# design.net
KiCad netlist of a schematic drawn in Altium Designer
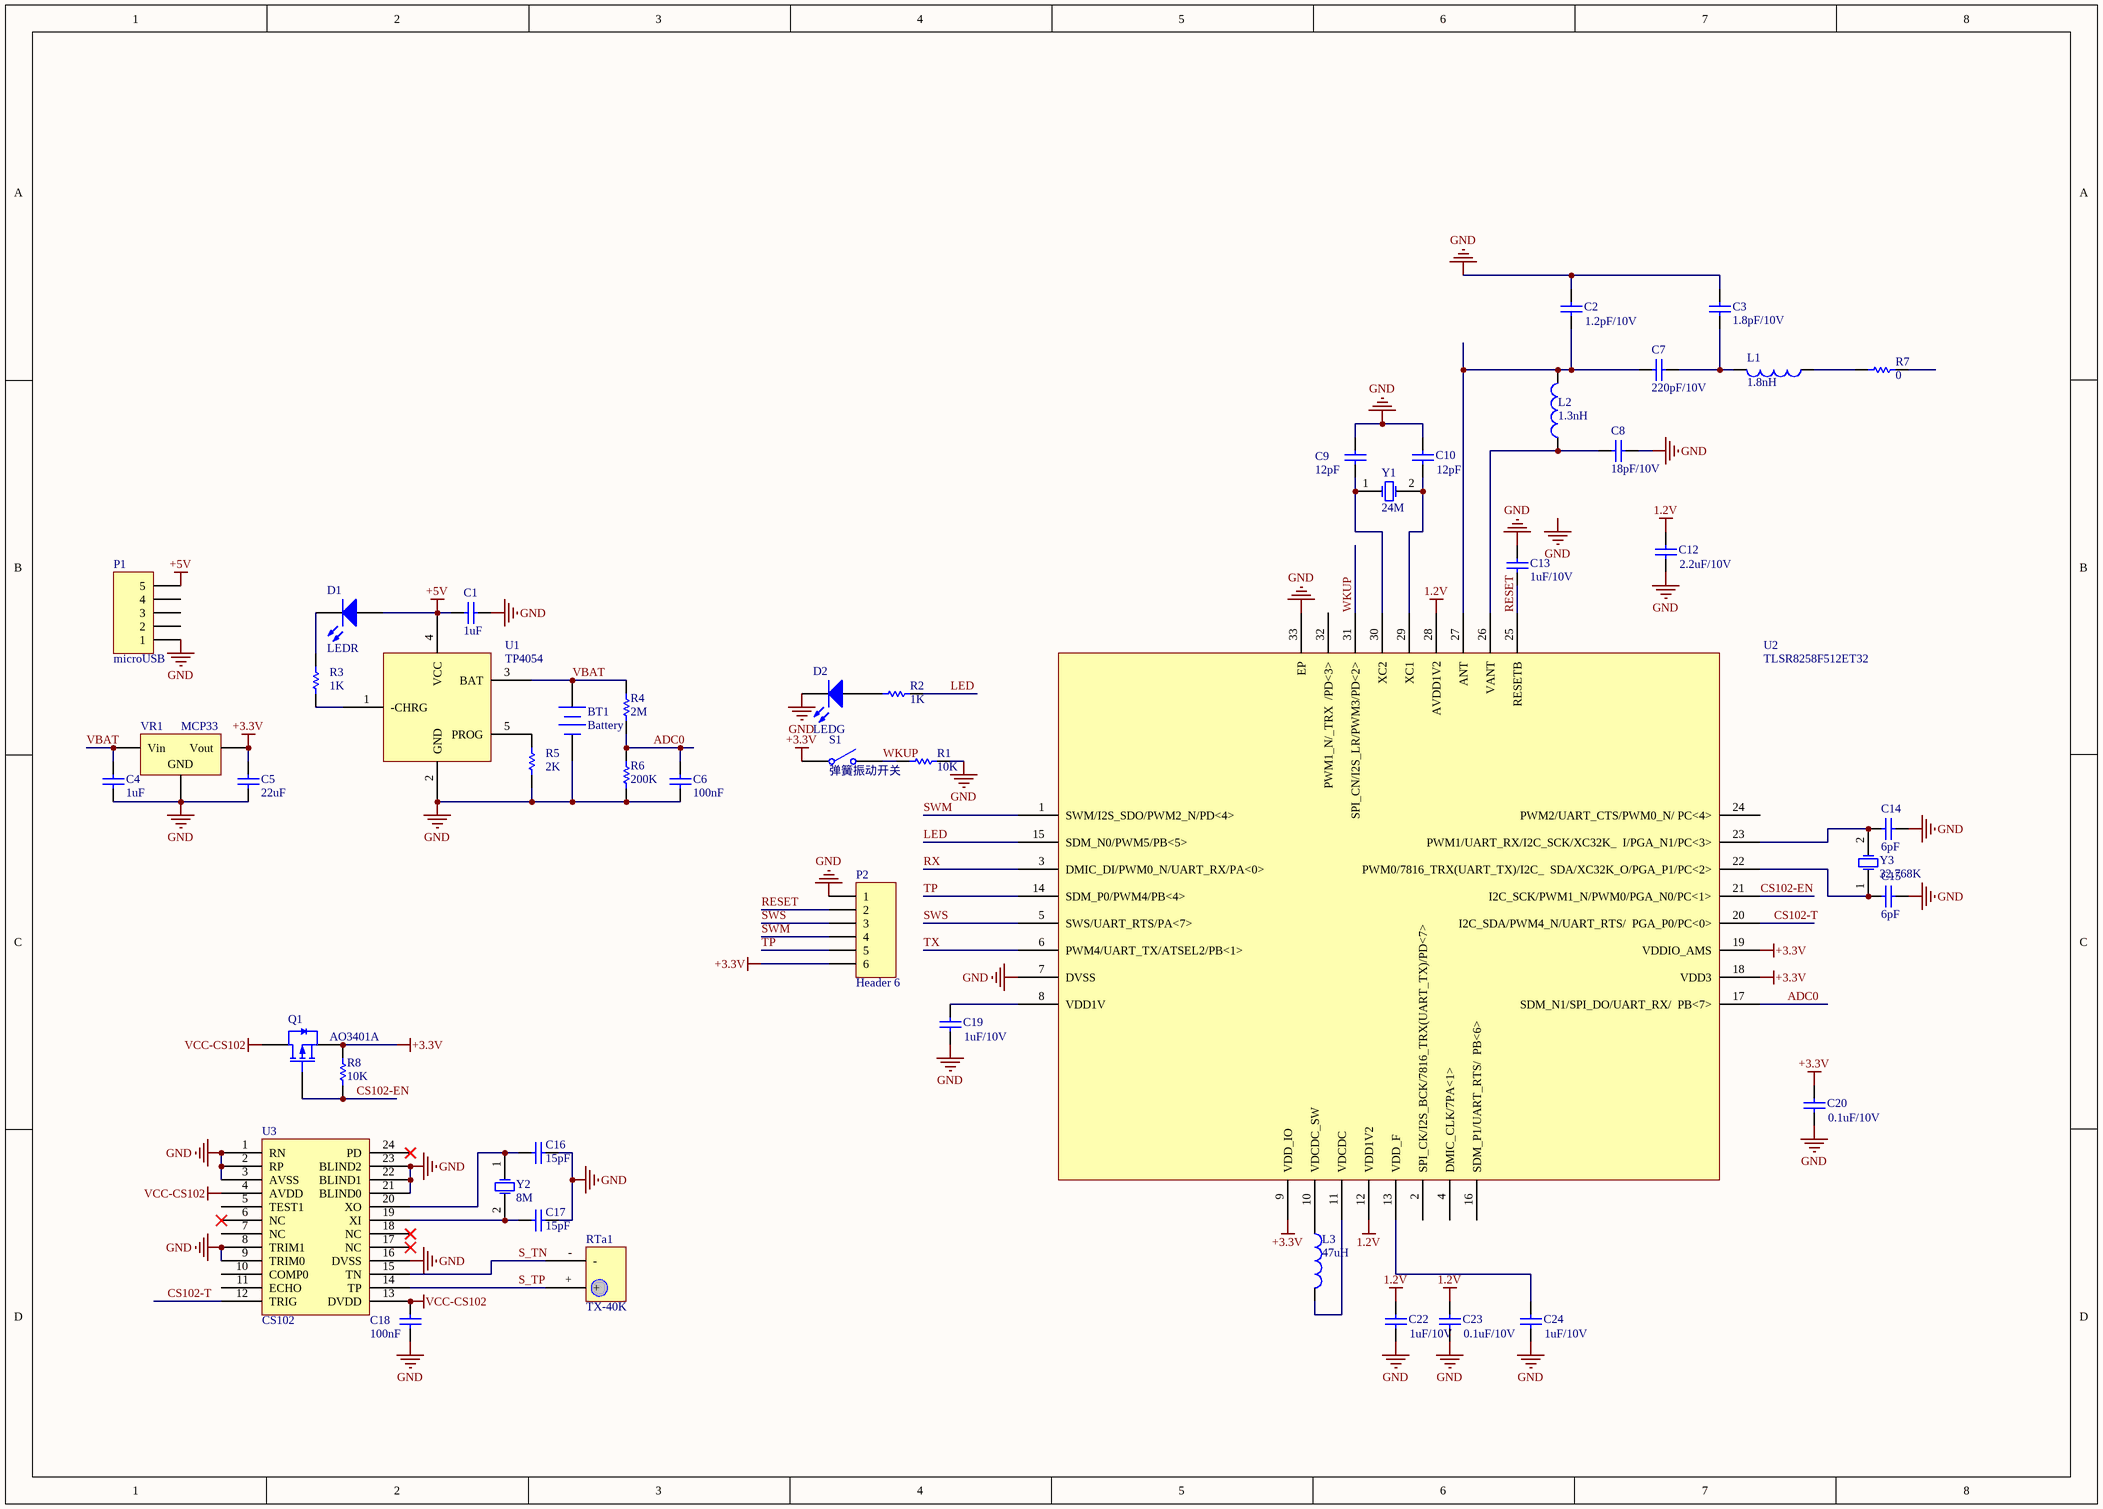
[diagram p0: 发送端原理图.SchDoc]

(export (version "E")
  (design (tool "Eeschema 10.0.6"))
  (components
    (comp (ref "BT1")
      (value "Battery")
      (footprint "BT")
      (description "Multicell Battery")
      (fields (field (name "PUBLISHER") "Altium Limited"))
      (libsource (lib "Miscellaneous Devices") (part "Battery"))
    )
    (comp (ref "C1")
      (value "1uF")
      (description "Capacitor")
      (fields (field (name "PUBLISHER") "Altium Limited"))
      (libsource (lib "Miscellaneous Devices") (part "Cap"))
    )
    (comp (ref "C2")
      (value "1.2pF/10V")
      (footprint "0402")
      (description "Capacitor")
      (fields (field (name "PUBLISHER") "Altium Limited"))
      (libsource (lib "Miscellaneous Devices") (part "Cap"))
    )
    (comp (ref "C3")
      (value "1.8pF/10V")
      (footprint "0402")
      (description "Capacitor")
      (fields (field (name "PUBLISHER") "Altium Limited"))
      (libsource (lib "Miscellaneous Devices") (part "Cap"))
    )
    (comp (ref "C4")
      (value "1uF")
      (description "Capacitor")
      (fields (field (name "PUBLISHER") "Altium Limited"))
      (libsource (lib "Miscellaneous Devices") (part "Cap"))
    )
    (comp (ref "C5")
      (value "22uF")
      (description "Capacitor")
      (fields (field (name "PUBLISHER") "Altium Limited"))
      (libsource (lib "Miscellaneous Devices") (part "Cap"))
    )
    (comp (ref "C6")
      (value "100nF")
      (description "Capacitor")
      (fields (field (name "PUBLISHER") "Altium Limited"))
      (libsource (lib "Miscellaneous Devices") (part "Cap"))
    )
    (comp (ref "C7")
      (value "220pF/10V")
      (footprint "0402")
      (description "Capacitor")
      (fields (field (name "PUBLISHER") "Altium Limited"))
      (libsource (lib "Miscellaneous Devices") (part "Cap"))
    )
    (comp (ref "C8")
      (value "18pF/10V")
      (footprint "0402")
      (description "Capacitor")
      (fields (field (name "PUBLISHER") "Altium Limited"))
      (libsource (lib "Miscellaneous Devices") (part "Cap"))
    )
    (comp (ref "C9")
      (value "12pF")
      (footprint "0402")
      (description "Capacitor")
      (fields (field (name "PUBLISHER") "Altium Limited"))
      (libsource (lib "Miscellaneous Devices") (part "Cap"))
    )
    (comp (ref "C10")
      (value "12pF")
      (footprint "0402")
      (description "Capacitor")
      (fields (field (name "PUBLISHER") "Altium Limited"))
      (libsource (lib "Miscellaneous Devices") (part "Cap"))
    )
    (comp (ref "C12")
      (value "2.2uF/10V")
      (footprint "0402")
      (description "Capacitor")
      (fields (field (name "PUBLISHER") "Altium Limited"))
      (libsource (lib "Miscellaneous Devices") (part "Cap"))
    )
    (comp (ref "C13")
      (value "1uF/10V")
      (footprint "0402")
      (description "Capacitor")
      (fields (field (name "PUBLISHER") "Altium Limited"))
      (libsource (lib "Miscellaneous Devices") (part "Cap"))
    )
    (comp (ref "C14")
      (value "6pF")
      (footprint "0402")
      (description "Capacitor")
      (fields (field (name "PUBLISHER") "Altium Limited"))
      (libsource (lib "Miscellaneous Devices") (part "Cap"))
    )
    (comp (ref "C15")
      (value "6pF")
      (footprint "0402")
      (description "Capacitor")
      (fields (field (name "PUBLISHER") "Altium Limited"))
      (libsource (lib "Miscellaneous Devices") (part "Cap"))
    )
    (comp (ref "C16")
      (value "15pF")
      (footprint "0402")
      (description "Capacitor")
      (fields (field (name "PUBLISHER") "Altium Limited"))
      (libsource (lib "Miscellaneous Devices") (part "Cap"))
    )
    (comp (ref "C17")
      (value "15pF")
      (footprint "0402")
      (description "Capacitor")
      (fields (field (name "PUBLISHER") "Altium Limited"))
      (libsource (lib "Miscellaneous Devices") (part "Cap"))
    )
    (comp (ref "C18")
      (value "100nF")
      (description "Capacitor")
      (fields (field (name "PUBLISHER") "Altium Limited"))
      (libsource (lib "Miscellaneous Devices") (part "Cap"))
    )
    (comp (ref "C19")
      (value "1uF/10V")
      (footprint "0402")
      (description "Capacitor")
      (fields (field (name "PUBLISHER") "Altium Limited"))
      (libsource (lib "Miscellaneous Devices") (part "Cap"))
    )
    (comp (ref "C20")
      (value "0.1uF/10V")
      (footprint "0402")
      (description "Capacitor")
      (fields (field (name "PUBLISHER") "Altium Limited"))
      (libsource (lib "Miscellaneous Devices") (part "Cap"))
    )
    (comp (ref "C22")
      (value "1uF/10V")
      (footprint "0402")
      (description "Capacitor")
      (fields (field (name "PUBLISHER") "Altium Limited"))
      (libsource (lib "Miscellaneous Devices") (part "Cap"))
    )
    (comp (ref "C23")
      (value "0.1uF/10V")
      (footprint "0402")
      (description "Capacitor")
      (fields (field (name "PUBLISHER") "Altium Limited"))
      (libsource (lib "Miscellaneous Devices") (part "Cap"))
    )
    (comp (ref "C24")
      (value "1uF/10V")
      (footprint "0402")
      (description "Capacitor")
      (fields (field (name "PUBLISHER") "Altium Limited"))
      (libsource (lib "Miscellaneous Devices") (part "Cap"))
    )
    (comp (ref "D1")
      (value "LEDR")
      (footprint "LED0603")
      (description "Typical INFRARED GaAs LED")
      (fields (field (name "PUBLISHER") "Altium Limited"))
      (libsource (lib "Miscellaneous Devices") (part "LED0"))
    )
    (comp (ref "D2")
      (value "LEDG")
      (footprint "LED0603")
      (description "Typical INFRARED GaAs LED")
      (fields (field (name "PUBLISHER") "Altium Limited"))
      (libsource (lib "Miscellaneous Devices") (part "LED0"))
    )
    (comp (ref "L1")
      (value "1.8nH")
      (description "Inductor")
      (fields (field (name "PUBLISHER") "Altium Limited"))
      (libsource (lib "Miscellaneous Devices") (part "Inductor"))
    )
    (comp (ref "L2")
      (value "1.3nH")
      (description "Inductor")
      (fields (field (name "PUBLISHER") "Altium Limited"))
      (libsource (lib "Miscellaneous Devices") (part "Inductor"))
    )
    (comp (ref "L3")
      (value "47uH")
      (footprint "0603R")
      (description "Inductor")
      (fields (field (name "PUBLISHER") "Altium Limited"))
      (libsource (lib "Miscellaneous Devices") (part "Inductor"))
    )
    (comp (ref "P1")
      (value "microUSB")
      (footprint "MICROUSB")
      (description "Header, 5-Pin")
      (fields (field (name "PUBLISHER") "Altium Limited"))
      (libsource (lib "Miscellaneous Connectors") (part "Header 5"))
    )
    (comp (ref "P2")
      (value "Header 6")
      (footprint "SIP6-1.27")
      (description "Header, 6-Pin")
      (fields (field (name "PUBLISHER") "Altium Limited"))
      (libsource (lib "Miscellaneous Connectors") (part "Header 6"))
    )
    (comp (ref "Q1")
      (value "AO3401A")
      (footprint "AO3401")
      (description "MOS(场效应管)")
      (libsource (lib "Miscellaneous Devices LC") (part "AO3401A P道沟 X13A15 SOT-23"))
    )
    (comp (ref "R1")
      (value "10K")
      (description "Resistor")
      (fields (field (name "PUBLISHER") "Altium Limited"))
      (libsource (lib "Miscellaneous Devices") (part "Res1"))
    )
    (comp (ref "R2")
      (value "1K")
      (description "Resistor")
      (fields (field (name "PUBLISHER") "Altium Limited"))
      (libsource (lib "Miscellaneous Devices") (part "Res1"))
    )
    (comp (ref "R3")
      (value "1K")
      (description "Resistor")
      (fields (field (name "PUBLISHER") "Altium Limited"))
      (libsource (lib "Miscellaneous Devices") (part "Res1"))
    )
    (comp (ref "R4")
      (value "2M")
      (description "Resistor")
      (fields (field (name "PUBLISHER") "Altium Limited"))
      (libsource (lib "Miscellaneous Devices") (part "Res1"))
    )
    (comp (ref "R5")
      (value "2K")
      (description "Resistor")
      (fields (field (name "PUBLISHER") "Altium Limited"))
      (libsource (lib "Miscellaneous Devices") (part "Res1"))
    )
    (comp (ref "R6")
      (value "200K")
      (description "Resistor")
      (fields (field (name "PUBLISHER") "Altium Limited"))
      (libsource (lib "Miscellaneous Devices") (part "Res1"))
    )
    (comp (ref "R7")
      (value "0")
      (description "Resistor")
      (fields (field (name "PUBLISHER") "Altium Limited"))
      (libsource (lib "Miscellaneous Devices") (part "Res1"))
    )
    (comp (ref "R8")
      (value "10K")
      (description "Resistor")
      (fields (field (name "PUBLISHER") "Altium Limited"))
      (libsource (lib "Miscellaneous Devices") (part "Res1"))
    )
    (comp (ref "RTa1") (value "TX-40K") (footprint "US-10mm") (libsource (lib "USLib") (part "TC40K")))
    (comp (ref "S1")
      (value "弹簧振动开关")
      (footprint "SW")
      (description "Single-Pole, Single-Throw Switch")
      (fields (field (name "PUBLISHER") "Altium Limited"))
      (libsource (lib "Miscellaneous Devices") (part "SW-SPST"))
    )
    (comp (ref "U1") (value "TP4054") (footprint "TP4054") (libsource (lib "Schlib1") (part "TP4054")))
    (comp (ref "U2")
      (value "TLSR8258F512ET32")
      (footprint "QFN-32")
      (libsource (lib "stm32") (part "TLSR8258F512ET32"))
    )
    (comp (ref "U3") (value "CS102") (footprint "TSSOP24") (libsource (lib "USLib") (part "CS100")))
    (comp (ref "VR1")
      (value "MCP33")
      (footprint "MCP33")
      (description "Voltage Regulator")
      (fields (field (name "PUBLISHER") "Altium Limited"))
      (libsource (lib "Miscellaneous Devices") (part "Volt Reg"))
    )
    (comp (ref "Y1")
      (value "24M")
      (footprint "XTAL4TN_3225")
      (description "Crystal Oscillator")
      (fields (field (name "PUBLISHER") "Altium Limited"))
      (libsource (lib "Miscellaneous Devices") (part "XTAL"))
    )
    (comp (ref "Y2")
      (value "8M")
      (footprint "5032")
      (description "Crystal Oscillator")
      (fields (field (name "PUBLISHER") "Altium Limited"))
      (libsource (lib "Miscellaneous Devices") (part "XTAL"))
    )
    (comp (ref "Y3")
      (value "32.768K")
      (footprint "XTAL3215")
      (description "Crystal Oscillator")
      (fields (field (name "PUBLISHER") "Altium Limited"))
      (libsource (lib "Miscellaneous Devices") (part "XTAL"))
    )
  )
  (nets
    (net (code "1") (name "+3.3V") (class "Default")
      (node (ref "C20") (pin "2") (pinfunction "2_2") (pintype "passive"))
      (node (ref "C5") (pin "1") (pinfunction "1_1") (pintype "passive"))
      (node (ref "P2") (pin "6") (pinfunction "6_6") (pintype "passive"))
      (node (ref "Q1") (pin "2") (pinfunction "S_2") (pintype "passive"))
      (node (ref "R8") (pin "2") (pinfunction "2_2") (pintype "passive"))
      (node (ref "S1") (pin "1") (pinfunction "COMMON_1") (pintype "passive"))
      (node (ref "U2") (pin "18") (pinfunction "VDD3_18") (pintype "passive"))
      (node (ref "U2") (pin "19") (pinfunction "VDDIO_AMS_19") (pintype "passive"))
      (node (ref "U2") (pin "9") (pinfunction "VDD_IO_9") (pintype "passive"))
      (node (ref "VR1") (pin "3") (pinfunction "Vout_3") (pintype "passive"))
    )
    (net (code "2") (name "+5V") (class "Default")
      (node (ref "C1") (pin "2") (pinfunction "2_2") (pintype "passive"))
      (node (ref "D1") (pin "1") (pinfunction "A_1") (pintype "passive"))
      (node (ref "P1") (pin "5") (pinfunction "5_5") (pintype "passive"))
      (node (ref "U1") (pin "4") (pinfunction "VCC_4") (pintype "passive"))
    )
    (net (code "3") (name "/ADC0") (class "Default")
      (node (ref "C6") (pin "2") (pinfunction "2_2") (pintype "passive"))
      (node (ref "R4") (pin "1") (pinfunction "1_1") (pintype "passive"))
      (node (ref "R6") (pin "2") (pinfunction "2_2") (pintype "passive"))
      (node (ref "U2") (pin "17") (pinfunction "SDM_N1/SPI_DO/UART_RX/__PB<7>_17") (pintype "passive"))
    )
    (net (code "4") (name "/CS102-EN") (class "Default")
      (node (ref "Q1") (pin "1") (pinfunction "G_1") (pintype "passive"))
      (node (ref "R8") (pin "1") (pinfunction "1_1") (pintype "passive"))
      (node (ref "U2") (pin "21") (pinfunction "I2C_SCK/PWM1_N/PWM0/PGA_N0/PC<1>_21") (pintype "passive"))
    )
    (net (code "5") (name "/CS102-T") (class "Default")
      (node (ref "U2") (pin "20") (pinfunction "I2C_SDA/PWM4_N/UART_RTS/__PGA_P0/PC<0>_20") (pintype "passive"))
      (node (ref "U3") (pin "12") (pinfunction "TRIG_12") (pintype "passive"))
    )
    (net (code "6") (name "/LED") (class "Default")
      (node (ref "R2") (pin "1") (pinfunction "1_1") (pintype "passive"))
      (node (ref "U2") (pin "15") (pinfunction "SDM_N0/PWM5/PB<5>_15") (pintype "passive"))
    )
    (net (code "7") (name "/RESET") (class "Default")
      (node (ref "C13") (pin "2") (pinfunction "2_2") (pintype "passive"))
      (node (ref "P2") (pin "2") (pinfunction "2_2") (pintype "passive"))
      (node (ref "U2") (pin "25") (pinfunction "RESETB_25") (pintype "passive"))
    )
    (net (code "8") (name "/RX") (class "Default")
      (node (ref "U2") (pin "3") (pinfunction "DMIC_DI/PWM0_N/UART_RX/PA<0>_3") (pintype "passive"))
    )
    (net (code "9") (name "/SWM") (class "Default")
      (node (ref "P2") (pin "4") (pinfunction "4_4") (pintype "passive"))
      (node (ref "U2") (pin "1") (pinfunction "SWM/I2S_SDO/PWM2_N/PD<4>_1") (pintype "passive"))
    )
    (net (code "10") (name "/SWS") (class "Default")
      (node (ref "P2") (pin "3") (pinfunction "3_3") (pintype "passive"))
      (node (ref "U2") (pin "5") (pinfunction "SWS/UART_RTS/PA<7>_5") (pintype "passive"))
    )
    (net (code "11") (name "/S_TN") (class "Default")
      (node (ref "RTa1") (pin "-") (pinfunction "-_-") (pintype "passive"))
      (node (ref "U3") (pin "15") (pinfunction "TN_15") (pintype "passive"))
    )
    (net (code "12") (name "/S_TP") (class "Default")
      (node (ref "RTa1") (pin "+") (pinfunction "+_+") (pintype "passive"))
      (node (ref "U3") (pin "14") (pinfunction "TP_14") (pintype "passive"))
    )
    (net (code "13") (name "/TP") (class "Default")
      (node (ref "P2") (pin "5") (pinfunction "5_5") (pintype "passive"))
      (node (ref "U2") (pin "14") (pinfunction "SDM_P0/PWM4/PB<4>_14") (pintype "passive"))
    )
    (net (code "14") (name "/TX") (class "Default")
      (node (ref "U2") (pin "6") (pinfunction "PWM4/UART_TX/ATSEL2/PB<1>_6") (pintype "passive"))
    )
    (net (code "15") (name "/VBAT") (class "Default")
      (node (ref "BT1") (pin "1") (pinfunction "+_1") (pintype "passive"))
      (node (ref "C4") (pin "1") (pinfunction "1_1") (pintype "passive"))
      (node (ref "R4") (pin "2") (pinfunction "2_2") (pintype "passive"))
      (node (ref "U1") (pin "3") (pinfunction "BAT_3") (pintype "passive"))
      (node (ref "VR1") (pin "1") (pinfunction "Vin_1") (pintype "passive"))
    )
    (net (code "16") (name "/WKUP") (class "Default")
      (node (ref "R1") (pin "2") (pinfunction "2_2") (pintype "passive"))
      (node (ref "S1") (pin "2") (pinfunction "NO_2") (pintype "passive"))
      (node (ref "U2") (pin "31") (pinfunction "SPI_CN/I2S_LR/PWM3/PD<2>_31") (pintype "passive"))
    )
    (net (code "17") (name "1.2V") (class "Default")
      (node (ref "C12") (pin "2") (pinfunction "2_2") (pintype "passive"))
      (node (ref "C22") (pin "2") (pinfunction "2_2") (pintype "passive"))
      (node (ref "C23") (pin "2") (pinfunction "2_2") (pintype "passive"))
      (node (ref "U2") (pin "12") (pinfunction "VDD1V2_12") (pintype "passive"))
      (node (ref "U2") (pin "28") (pinfunction "AVDD1V2_28") (pintype "passive"))
    )
    (net (code "18") (name "GND") (class "Default")
      (node (ref "BT1") (pin "2") (pinfunction "-_2") (pintype "passive"))
      (node (ref "C1") (pin "1") (pinfunction "1_1") (pintype "passive"))
      (node (ref "C10") (pin "2") (pinfunction "2_2") (pintype "passive"))
      (node (ref "C12") (pin "1") (pinfunction "1_1") (pintype "passive"))
      (node (ref "C13") (pin "1") (pinfunction "1_1") (pintype "passive"))
      (node (ref "C14") (pin "1") (pinfunction "1_1") (pintype "passive"))
      (node (ref "C15") (pin "1") (pinfunction "1_1") (pintype "passive"))
      (node (ref "C16") (pin "2") (pinfunction "2_2") (pintype "passive"))
      (node (ref "C17") (pin "2") (pinfunction "2_2") (pintype "passive"))
      (node (ref "C18") (pin "1") (pinfunction "1_1") (pintype "passive"))
      (node (ref "C19") (pin "1") (pinfunction "1_1") (pintype "passive"))
      (node (ref "C2") (pin "2") (pinfunction "2_2") (pintype "passive"))
      (node (ref "C20") (pin "1") (pinfunction "1_1") (pintype "passive"))
      (node (ref "C22") (pin "1") (pinfunction "1_1") (pintype "passive"))
      (node (ref "C23") (pin "1") (pinfunction "1_1") (pintype "passive"))
      (node (ref "C24") (pin "1") (pinfunction "1_1") (pintype "passive"))
      (node (ref "C3") (pin "1") (pinfunction "1_1") (pintype "passive"))
      (node (ref "C4") (pin "2") (pinfunction "2_2") (pintype "passive"))
      (node (ref "C5") (pin "2") (pinfunction "2_2") (pintype "passive"))
      (node (ref "C6") (pin "1") (pinfunction "1_1") (pintype "passive"))
      (node (ref "C8") (pin "1") (pinfunction "1_1") (pintype "passive"))
      (node (ref "C9") (pin "2") (pinfunction "2_2") (pintype "passive"))
      (node (ref "D2") (pin "2") (pinfunction "K_2") (pintype "passive"))
      (node (ref "P1") (pin "1") (pinfunction "1_1") (pintype "passive"))
      (node (ref "P2") (pin "1") (pinfunction "1_1") (pintype "passive"))
      (node (ref "R1") (pin "1") (pinfunction "1_1") (pintype "passive"))
      (node (ref "R5") (pin "1") (pinfunction "1_1") (pintype "passive"))
      (node (ref "R6") (pin "1") (pinfunction "1_1") (pintype "passive"))
      (node (ref "U1") (pin "2") (pinfunction "GND_2") (pintype "passive"))
      (node (ref "U2") (pin "33") (pinfunction "EP_33") (pintype "passive"))
      (node (ref "U2") (pin "7") (pinfunction "DVSS_7") (pintype "passive"))
      (node (ref "U3") (pin "1") (pinfunction "RN_1") (pintype "passive"))
      (node (ref "U3") (pin "16") (pinfunction "DVSS_16") (pintype "passive"))
      (node (ref "U3") (pin "2") (pinfunction "RP_2") (pintype "passive"))
      (node (ref "U3") (pin "21") (pinfunction "BLIND0_21") (pintype "passive"))
      (node (ref "U3") (pin "22") (pinfunction "BLIND1_22") (pintype "passive"))
      (node (ref "U3") (pin "23") (pinfunction "BLIND2_23") (pintype "passive"))
      (node (ref "U3") (pin "3") (pinfunction "AVSS_3") (pintype "passive"))
      (node (ref "U3") (pin "8") (pinfunction "TRIM1_8") (pintype "passive"))
      (node (ref "U3") (pin "9") (pinfunction "TRIM0_9") (pintype "passive"))
      (node (ref "VR1") (pin "2") (pinfunction "GND_2") (pintype "passive"))
    )
    (net (code "19") (name "Net-(C3-Pad2)") (class "Default")
      (node (ref "C3") (pin "2") (pinfunction "2_2") (pintype "passive"))
      (node (ref "C7") (pin "1") (pinfunction "1_1") (pintype "passive"))
      (node (ref "L1") (pin "2") (pinfunction "2_2") (pintype "passive"))
    )
    (net (code "20") (name "Net-(D1-K)") (class "Default")
      (node (ref "D1") (pin "2") (pinfunction "K_2") (pintype "passive"))
      (node (ref "R3") (pin "2") (pinfunction "2_2") (pintype "passive"))
    )
    (net (code "21") (name "Net-(D2-A)") (class "Default")
      (node (ref "D2") (pin "1") (pinfunction "A_1") (pintype "passive"))
      (node (ref "R2") (pin "2") (pinfunction "2_2") (pintype "passive"))
    )
    (net (code "22") (name "Net-(L1-Pad1)") (class "Default")
      (node (ref "L1") (pin "1") (pinfunction "1_1") (pintype "passive"))
      (node (ref "R7") (pin "2") (pinfunction "2_2") (pintype "passive"))
    )
    (net (code "23") (name "Net-(U1--CHRG)") (class "Default")
      (node (ref "R3") (pin "1") (pinfunction "1_1") (pintype "passive"))
      (node (ref "U1") (pin "1") (pinfunction "-CHRG_1") (pintype "passive"))
    )
    (net (code "24") (name "Net-(U1-PROG)") (class "Default")
      (node (ref "R5") (pin "2") (pinfunction "2_2") (pintype "passive"))
      (node (ref "U1") (pin "5") (pinfunction "PROG_5") (pintype "passive"))
    )
    (net (code "25") (name "Net-(U2-ANT)") (class "Default")
      (node (ref "C2") (pin "1") (pinfunction "1_1") (pintype "passive"))
      (node (ref "C7") (pin "2") (pinfunction "2_2") (pintype "passive"))
      (node (ref "L2") (pin "2") (pinfunction "2_2") (pintype "passive"))
      (node (ref "U2") (pin "27") (pinfunction "ANT_27") (pintype "passive"))
    )
    (net (code "26") (name "Net-(U2-PWM0{slash}7816_TRX(UART_TX){slash}I2C___SDA{slash}XC32K_O{slash}PGA_P1{slash}PC<2>)") (class "Default")
      (node (ref "C15") (pin "2") (pinfunction "2_2") (pintype "passive"))
      (node (ref "U2") (pin "22") (pinfunction "PWM0/7816_TRX(UART_TX)/I2C___SDA/XC32K_O/PGA_P1/PC<2>_22") (pintype "passive"))
      (node (ref "Y3") (pin "1") (pinfunction "OSC1_1") (pintype "passive"))
    )
    (net (code "27") (name "Net-(U2-PWM1{slash}UART_RX{slash}I2C_SCK{slash}XC32K___I{slash}PGA_N1{slash}PC<3>)") (class "Default")
      (node (ref "C14") (pin "2") (pinfunction "2_2") (pintype "passive"))
      (node (ref "U2") (pin "23") (pinfunction "PWM1/UART_RX/I2C_SCK/XC32K___I/PGA_N1/PC<3>_23") (pintype "passive"))
      (node (ref "Y3") (pin "2") (pinfunction "OSC2_2") (pintype "passive"))
    )
    (net (code "28") (name "Net-(U2-VANT)") (class "Default")
      (node (ref "C8") (pin "2") (pinfunction "2_2") (pintype "passive"))
      (node (ref "L2") (pin "1") (pinfunction "1_1") (pintype "passive"))
      (node (ref "U2") (pin "26") (pinfunction "VANT_26") (pintype "passive"))
    )
    (net (code "29") (name "Net-(U2-VDCDC)") (class "Default")
      (node (ref "L3") (pin "2") (pinfunction "2_2") (pintype "passive"))
      (node (ref "U2") (pin "11") (pinfunction "VDCDC_11") (pintype "passive"))
    )
    (net (code "30") (name "Net-(U2-VDCDC_SW)") (class "Default")
      (node (ref "L3") (pin "1") (pinfunction "1_1") (pintype "passive"))
      (node (ref "U2") (pin "10") (pinfunction "VDCDC_SW_10") (pintype "passive"))
    )
    (net (code "31") (name "Net-(U2-VDD1V)") (class "Default")
      (node (ref "C19") (pin "2") (pinfunction "2_2") (pintype "passive"))
      (node (ref "U2") (pin "8") (pinfunction "VDD1V_8") (pintype "passive"))
    )
    (net (code "32") (name "Net-(U2-VDD_F)") (class "Default")
      (node (ref "C24") (pin "2") (pinfunction "2_2") (pintype "passive"))
      (node (ref "U2") (pin "13") (pinfunction "VDD_F_13") (pintype "passive"))
    )
    (net (code "33") (name "Net-(U2-XC1)") (class "Default")
      (node (ref "C10") (pin "1") (pinfunction "1_1") (pintype "passive"))
      (node (ref "U2") (pin "29") (pinfunction "XC1_29") (pintype "passive"))
      (node (ref "Y1") (pin "2") (pinfunction "OSC2_2") (pintype "passive"))
    )
    (net (code "34") (name "Net-(U2-XC2)") (class "Default")
      (node (ref "C9") (pin "1") (pinfunction "1_1") (pintype "passive"))
      (node (ref "U2") (pin "30") (pinfunction "XC2_30") (pintype "passive"))
      (node (ref "Y1") (pin "1") (pinfunction "OSC1_1") (pintype "passive"))
    )
    (net (code "35") (name "Net-(U3-XI)") (class "Default")
      (node (ref "C17") (pin "1") (pinfunction "1_1") (pintype "passive"))
      (node (ref "U3") (pin "19") (pinfunction "XI_19") (pintype "passive"))
      (node (ref "Y2") (pin "2") (pinfunction "OSC2_2") (pintype "passive"))
    )
    (net (code "36") (name "Net-(U3-XO)") (class "Default")
      (node (ref "C16") (pin "1") (pinfunction "1_1") (pintype "passive"))
      (node (ref "U3") (pin "20") (pinfunction "XO_20") (pintype "passive"))
      (node (ref "Y2") (pin "1") (pinfunction "OSC1_1") (pintype "passive"))
    )
    (net (code "37") (name "VCC-CS102") (class "Default")
      (node (ref "C18") (pin "2") (pinfunction "2_2") (pintype "passive"))
      (node (ref "Q1") (pin "3") (pinfunction "D_3") (pintype "passive"))
      (node (ref "U3") (pin "13") (pinfunction "DVDD_13") (pintype "passive"))
      (node (ref "U3") (pin "4") (pinfunction "AVDD_4") (pintype "passive"))
    )
    (net (code "38") (name "unconnected-(P1-Pad2)") (class "Default")
      (node (ref "P1") (pin "2") (pinfunction "2_2") (pintype "passive"))
    )
    (net (code "39") (name "unconnected-(P1-Pad3)") (class "Default")
      (node (ref "P1") (pin "3") (pinfunction "3_3") (pintype "passive"))
    )
    (net (code "40") (name "unconnected-(P1-Pad4)") (class "Default")
      (node (ref "P1") (pin "4") (pinfunction "4_4") (pintype "passive"))
    )
    (net (code "41") (name "unconnected-(R7-Pad1)") (class "Default")
      (node (ref "R7") (pin "1") (pinfunction "1_1") (pintype "passive"))
    )
    (net (code "42") (name "unconnected-(U2-DMIC_CLK{slash}7PA<1>-Pad4)") (class "Default")
      (node (ref "U2") (pin "4") (pinfunction "DMIC_CLK/7PA<1>_4") (pintype "passive"))
    )
    (net (code "43") (name "unconnected-(U2-PWM1_N{slash}_TRX__{slash}PD<3>-Pad32)") (class "Default")
      (node (ref "U2") (pin "32") (pinfunction "PWM1_N/_TRX__/PD<3>_32") (pintype "passive"))
    )
    (net (code "44") (name "unconnected-(U2-PWM2{slash}UART_CTS{slash}PWM0_N{slash}_PC<4>-Pad24)") (class "Default")
      (node (ref "U2") (pin "24") (pinfunction "PWM2/UART_CTS/PWM0_N/_PC<4>_24") (pintype "passive"))
    )
    (net (code "45") (name "unconnected-(U2-SDM_P1{slash}UART_RTS{slash}__PB<6>-Pad16)") (class "Default")
      (node (ref "U2") (pin "16") (pinfunction "SDM_P1/UART_RTS/__PB<6>_16") (pintype "passive"))
    )
    (net (code "46") (name "unconnected-(U2-SPI_CK{slash}I2S_BCK{slash}7816_TRX(UART_TX){slash}PD<7>-Pad2)") (class "Default")
      (node (ref "U2") (pin "2") (pinfunction "SPI_CK/I2S_BCK/7816_TRX(UART_TX)/PD<7>_2") (pintype "passive"))
    )
    (net (code "47") (name "unconnected-(U3-COMP0-Pad10)") (class "Default")
      (node (ref "U3") (pin "10") (pinfunction "COMP0_10") (pintype "passive"))
    )
    (net (code "48") (name "unconnected-(U3-ECHO-Pad11)") (class "Default")
      (node (ref "U3") (pin "11") (pinfunction "ECHO_11") (pintype "passive"))
    )
    (net (code "49") (name "unconnected-(U3-NC-Pad6)") (class "Default")
      (node (ref "U3") (pin "6") (pinfunction "NC_6") (pintype "passive+no_connect"))
    )
    (net (code "50") (name "unconnected-(U3-NC-Pad7)") (class "Default")
      (node (ref "U3") (pin "7") (pinfunction "NC_7") (pintype "passive"))
    )
    (net (code "51") (name "unconnected-(U3-NC-Pad17)") (class "Default")
      (node (ref "U3") (pin "17") (pinfunction "NC_17") (pintype "passive+no_connect"))
    )
    (net (code "52") (name "unconnected-(U3-NC-Pad18)") (class "Default")
      (node (ref "U3") (pin "18") (pinfunction "NC_18") (pintype "passive+no_connect"))
    )
    (net (code "53") (name "unconnected-(U3-PD-Pad24)") (class "Default")
      (node (ref "U3") (pin "24") (pinfunction "PD_24") (pintype "passive+no_connect"))
    )
    (net (code "54") (name "unconnected-(U3-TEST1-Pad5)") (class "Default")
      (node (ref "U3") (pin "5") (pinfunction "TEST1_5") (pintype "passive"))
    )
  )
)
